# esp_sch.net
KiCad netlist of a schematic drawn in EAGLE
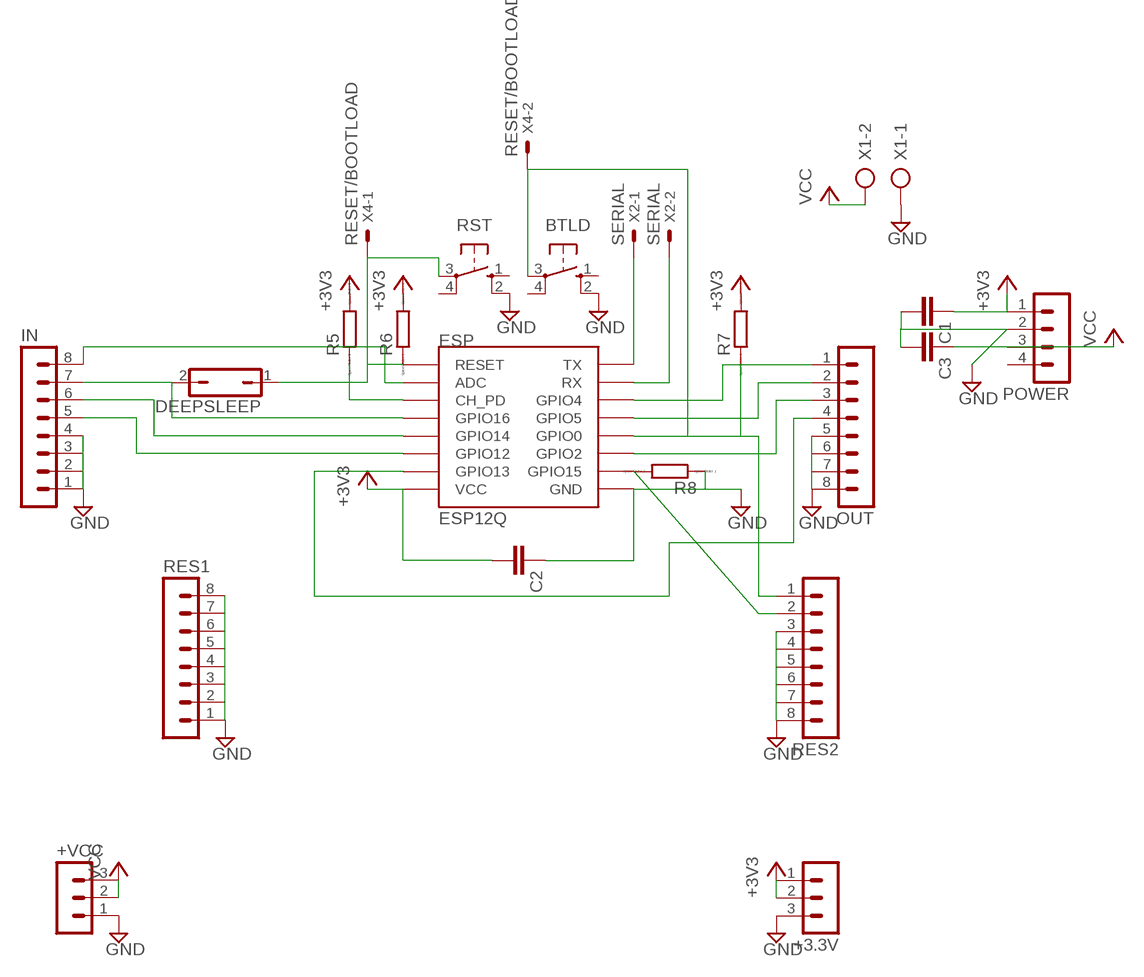
[diagram p0: schematic, sheet 1]

(export (version "E")
  (design (tool "Eeschema 10.0.6"))
  (components
    (comp (ref "+3.3V")
      (value "MA03-1")
      (footprint "eagle-import:MA03-1")
      (libsource (lib "eagle-import") (part "MA03-1"))
    )
    (comp (ref "+VCC")
      (value "MA03-1")
      (footprint "eagle-import:MA03-1")
      (libsource (lib "eagle-import") (part "MA03-1"))
    )
    (comp (ref "BTLD")
      (value "10-XX")
      (footprint "eagle-import:B3F-10XX")
      (fields (field (name "MPN") "B3F-1000"))
      (libsource (lib "eagle-import") (part "10-XX"))
    )
    (comp (ref "C1")
      (value "C-EU025-024X044")
      (footprint "eagle-import:C025-024X044")
      (libsource (lib "eagle-import") (part "C-EU025-024X044"))
    )
    (comp (ref "C2")
      (value "C-EU025-024X044")
      (footprint "eagle-import:C025-024X044")
      (libsource (lib "eagle-import") (part "C-EU025-024X044"))
    )
    (comp (ref "C3")
      (value "C-EU025-024X044")
      (footprint "eagle-import:C025-024X044")
      (libsource (lib "eagle-import") (part "C-EU025-024X044"))
    )
    (comp (ref "DEEPSLEEP")
      (value "JP1Q")
      (footprint "eagle-import:JP1")
      (libsource (lib "eagle-import") (part "JP1Q"))
    )
    (comp (ref "ESP")
      (value "ESP12Q")
      (footprint "eagle-import:ESP12Q")
      (libsource (lib "eagle-import") (part "ESP12Q"))
    )
    (comp (ref "IN")
      (value "MA08-1")
      (footprint "eagle-import:MA08-1")
      (libsource (lib "eagle-import") (part "MA08-1"))
    )
    (comp (ref "OUT")
      (value "MA08-1")
      (footprint "eagle-import:MA08-1")
      (libsource (lib "eagle-import") (part "MA08-1"))
    )
    (comp (ref "POWER")
      (value "MA04-1")
      (footprint "eagle-import:MA04-1")
      (libsource (lib "eagle-import") (part "MA04-1"))
    )
    (comp (ref "R5") (value "R") (footprint "eagle-import:R0805") (libsource (lib "eagle-import") (part "R")))
    (comp (ref "R6") (value "R") (footprint "eagle-import:R0805") (libsource (lib "eagle-import") (part "R")))
    (comp (ref "R7") (value "R") (footprint "eagle-import:R0805") (libsource (lib "eagle-import") (part "R")))
    (comp (ref "R8") (value "R") (footprint "eagle-import:R0805") (libsource (lib "eagle-import") (part "R")))
    (comp (ref "RES1")
      (value "MA08-1")
      (footprint "eagle-import:MA08-1")
      (libsource (lib "eagle-import") (part "MA08-1"))
    )
    (comp (ref "RES2")
      (value "MA08-1")
      (footprint "eagle-import:MA08-1")
      (libsource (lib "eagle-import") (part "MA08-1"))
    )
    (comp (ref "RST")
      (value "10-XX")
      (footprint "eagle-import:B3F-10XX")
      (fields (field (name "MPN") "B3F-1000"))
      (libsource (lib "eagle-import") (part "10-XX"))
    )
    (comp (ref "X1")
      (value "AK300/2")
      (footprint "eagle-import:AK300_2")
      (libsource (lib "eagle-import") (part "AK300/2"))
    )
    (comp (ref "X2")
      (value "SERIAL")
      (footprint "eagle-import:332-02")
      (libsource (lib "eagle-import") (part "332-02"))
    )
    (comp (ref "X4")
      (value "RESET/BOOTLOAD")
      (footprint "eagle-import:332-02")
      (libsource (lib "eagle-import") (part "332-02"))
    )
  )
  (nets
    (net (code "1") (name "+3V3") (class "Default")
      (node (ref "+3.3V") (pin "1") (pinfunction "1_1") (pintype "passive"))
      (node (ref "+3.3V") (pin "2") (pinfunction "2_2") (pintype "passive"))
      (node (ref "C1") (pin "1") (pinfunction "1_1") (pintype "passive"))
      (node (ref "C2") (pin "2") (pinfunction "2_2") (pintype "passive"))
      (node (ref "ESP") (pin "VCC") (pinfunction "VCC_VCC") (pintype "bidirectional"))
      (node (ref "POWER") (pin "1") (pinfunction "1_1") (pintype "passive"))
      (node (ref "R5") (pin "2") (pinfunction "2_2") (pintype "passive"))
      (node (ref "R6") (pin "2") (pinfunction "2_2") (pintype "passive"))
      (node (ref "R7") (pin "2") (pinfunction "2_2") (pintype "passive"))
    )
    (net (code "2") (name "GND") (class "Default")
      (node (ref "+3.3V") (pin "3") (pinfunction "3_3") (pintype "passive"))
      (node (ref "+VCC") (pin "1") (pinfunction "1_1") (pintype "passive"))
      (node (ref "BTLD") (pin "2") (pinfunction "S1_2") (pintype "passive"))
      (node (ref "C1") (pin "2") (pinfunction "2_2") (pintype "passive"))
      (node (ref "C2") (pin "1") (pinfunction "1_1") (pintype "passive"))
      (node (ref "C3") (pin "2") (pinfunction "2_2") (pintype "passive"))
      (node (ref "ESP") (pin "GND") (pinfunction "GND_GND") (pintype "bidirectional"))
      (node (ref "IN") (pin "1") (pinfunction "1_1") (pintype "passive"))
      (node (ref "IN") (pin "2") (pinfunction "2_2") (pintype "passive"))
      (node (ref "IN") (pin "3") (pinfunction "3_3") (pintype "passive"))
      (node (ref "IN") (pin "4") (pinfunction "4_4") (pintype "passive"))
      (node (ref "OUT") (pin "5") (pinfunction "5_5") (pintype "passive"))
      (node (ref "OUT") (pin "6") (pinfunction "6_6") (pintype "passive"))
      (node (ref "OUT") (pin "7") (pinfunction "7_7") (pintype "passive"))
      (node (ref "OUT") (pin "8") (pinfunction "8_8") (pintype "passive"))
      (node (ref "POWER") (pin "2") (pinfunction "2_2") (pintype "passive"))
      (node (ref "R8") (pin "1") (pinfunction "1_1") (pintype "passive"))
      (node (ref "RES1") (pin "1") (pinfunction "1_1") (pintype "passive"))
      (node (ref "RES1") (pin "2") (pinfunction "2_2") (pintype "passive"))
      (node (ref "RES1") (pin "3") (pinfunction "3_3") (pintype "passive"))
      (node (ref "RES1") (pin "4") (pinfunction "4_4") (pintype "passive"))
      (node (ref "RES1") (pin "5") (pinfunction "5_5") (pintype "passive"))
      (node (ref "RES1") (pin "6") (pinfunction "6_6") (pintype "passive"))
      (node (ref "RES1") (pin "7") (pinfunction "7_7") (pintype "passive"))
      (node (ref "RES1") (pin "8") (pinfunction "8_8") (pintype "passive"))
      (node (ref "RES2") (pin "3") (pinfunction "3_3") (pintype "passive"))
      (node (ref "RES2") (pin "4") (pinfunction "4_4") (pintype "passive"))
      (node (ref "RES2") (pin "5") (pinfunction "5_5") (pintype "passive"))
      (node (ref "RES2") (pin "6") (pinfunction "6_6") (pintype "passive"))
      (node (ref "RES2") (pin "7") (pinfunction "7_7") (pintype "passive"))
      (node (ref "RES2") (pin "8") (pinfunction "8_8") (pintype "passive"))
      (node (ref "RST") (pin "2") (pinfunction "S1_2") (pintype "passive"))
      (node (ref "X1") (pin "1") (pinfunction "KL_1") (pintype "passive"))
    )
    (net (code "3") (name "Net-(BTLD-P)") (class "Default")
      (node (ref "BTLD") (pin "3") (pinfunction "P_3") (pintype "passive"))
      (node (ref "ESP") (pin "GPIO0") (pinfunction "GPIO0_GPIO0") (pintype "bidirectional"))
      (node (ref "R7") (pin "1") (pinfunction "1_1") (pintype "passive"))
      (node (ref "RES2") (pin "1") (pinfunction "1_1") (pintype "passive"))
      (node (ref "X4") (pin "2") (pinfunction "S_2") (pintype "passive"))
    )
    (net (code "4") (name "Net-(DEEPSLEEP-Pad2)") (class "Default")
      (node (ref "DEEPSLEEP") (pin "2") (pinfunction "2_2") (pintype "passive"))
      (node (ref "ESP") (pin "GPIO16") (pinfunction "GPIO16_GPIO16") (pintype "bidirectional"))
      (node (ref "IN") (pin "7") (pinfunction "7_7") (pintype "passive"))
    )
    (net (code "5") (name "Net-(ESP-PadADC)") (class "Default")
      (node (ref "ESP") (pin "ADC") (pinfunction "ADC_ADC") (pintype "bidirectional"))
      (node (ref "IN") (pin "8") (pinfunction "8_8") (pintype "passive"))
    )
    (net (code "6") (name "Net-(ESP-PadCH_PD)") (class "Default")
      (node (ref "ESP") (pin "CH_PD") (pinfunction "CH_PD_CH_PD") (pintype "bidirectional"))
      (node (ref "R5") (pin "1") (pinfunction "1_1") (pintype "passive"))
    )
    (net (code "7") (name "Net-(ESP-PadGPIO2)") (class "Default")
      (node (ref "ESP") (pin "GPIO2") (pinfunction "GPIO2_GPIO2") (pintype "bidirectional"))
      (node (ref "OUT") (pin "3") (pinfunction "3_3") (pintype "passive"))
    )
    (net (code "8") (name "Net-(ESP-PadGPIO4)") (class "Default")
      (node (ref "ESP") (pin "GPIO4") (pinfunction "GPIO4_GPIO4") (pintype "bidirectional"))
      (node (ref "OUT") (pin "1") (pinfunction "1_1") (pintype "passive"))
    )
    (net (code "9") (name "Net-(ESP-PadGPIO5)") (class "Default")
      (node (ref "ESP") (pin "GPIO5") (pinfunction "GPIO5_GPIO5") (pintype "bidirectional"))
      (node (ref "OUT") (pin "2") (pinfunction "2_2") (pintype "passive"))
    )
    (net (code "10") (name "Net-(ESP-PadGPIO12)") (class "Default")
      (node (ref "ESP") (pin "GPIO12") (pinfunction "GPIO12_GPIO12") (pintype "bidirectional"))
      (node (ref "IN") (pin "5") (pinfunction "5_5") (pintype "passive"))
    )
    (net (code "11") (name "Net-(ESP-PadGPIO13)") (class "Default")
      (node (ref "ESP") (pin "GPIO13") (pinfunction "GPIO13_GPIO13") (pintype "bidirectional"))
      (node (ref "OUT") (pin "4") (pinfunction "4_4") (pintype "passive"))
    )
    (net (code "12") (name "Net-(ESP-PadGPIO14)") (class "Default")
      (node (ref "ESP") (pin "GPIO14") (pinfunction "GPIO14_GPIO14") (pintype "bidirectional"))
      (node (ref "IN") (pin "6") (pinfunction "6_6") (pintype "passive"))
    )
    (net (code "13") (name "Net-(ESP-PadGPIO15)") (class "Default")
      (node (ref "ESP") (pin "GPIO15") (pinfunction "GPIO15_GPIO15") (pintype "bidirectional"))
      (node (ref "R8") (pin "2") (pinfunction "2_2") (pintype "passive"))
      (node (ref "RES2") (pin "2") (pinfunction "2_2") (pintype "passive"))
    )
    (net (code "14") (name "Net-(RST-P)") (class "Default")
      (node (ref "DEEPSLEEP") (pin "1") (pinfunction "1_1") (pintype "passive"))
      (node (ref "ESP") (pin "RESET") (pinfunction "RESET_RESET") (pintype "bidirectional"))
      (node (ref "R6") (pin "1") (pinfunction "1_1") (pintype "passive"))
      (node (ref "RST") (pin "3") (pinfunction "P_3") (pintype "passive"))
      (node (ref "X4") (pin "1") (pinfunction "S_1") (pintype "passive"))
    )
    (net (code "15") (name "Net-(X2A-S)") (class "Default")
      (node (ref "ESP") (pin "TX") (pinfunction "TX_TX") (pintype "bidirectional"))
      (node (ref "X2") (pin "1") (pinfunction "S_1") (pintype "passive"))
    )
    (net (code "16") (name "Net-(X2B-S)") (class "Default")
      (node (ref "ESP") (pin "RX") (pinfunction "RX_RX") (pintype "bidirectional"))
      (node (ref "X2") (pin "2") (pinfunction "S_2") (pintype "passive"))
    )
    (net (code "17") (name "VCC") (class "Default")
      (node (ref "+VCC") (pin "2") (pinfunction "2_2") (pintype "passive"))
      (node (ref "+VCC") (pin "3") (pinfunction "3_3") (pintype "passive"))
      (node (ref "C3") (pin "1") (pinfunction "1_1") (pintype "passive"))
      (node (ref "POWER") (pin "3") (pinfunction "3_3") (pintype "passive"))
      (node (ref "X1") (pin "2") (pinfunction "KL_2") (pintype "passive"))
    )
    (net (code "18") (name "unconnected-(BTLD-P1-Pad4)") (class "Default")
      (node (ref "BTLD") (pin "4") (pinfunction "P1_4") (pintype "passive"))
    )
    (net (code "19") (name "unconnected-(BTLD-S-Pad1)") (class "Default")
      (node (ref "BTLD") (pin "1") (pinfunction "S_1") (pintype "passive"))
    )
    (net (code "20") (name "unconnected-(POWER-Pad4)") (class "Default")
      (node (ref "POWER") (pin "4") (pinfunction "4_4") (pintype "passive"))
    )
    (net (code "21") (name "unconnected-(RST-P1-Pad4)") (class "Default")
      (node (ref "RST") (pin "4") (pinfunction "P1_4") (pintype "passive"))
    )
    (net (code "22") (name "unconnected-(RST-S-Pad1)") (class "Default")
      (node (ref "RST") (pin "1") (pinfunction "S_1") (pintype "passive"))
    )
  )
)
